# Ver_5.net
KiCad netlist of a schematic drawn in EAGLE
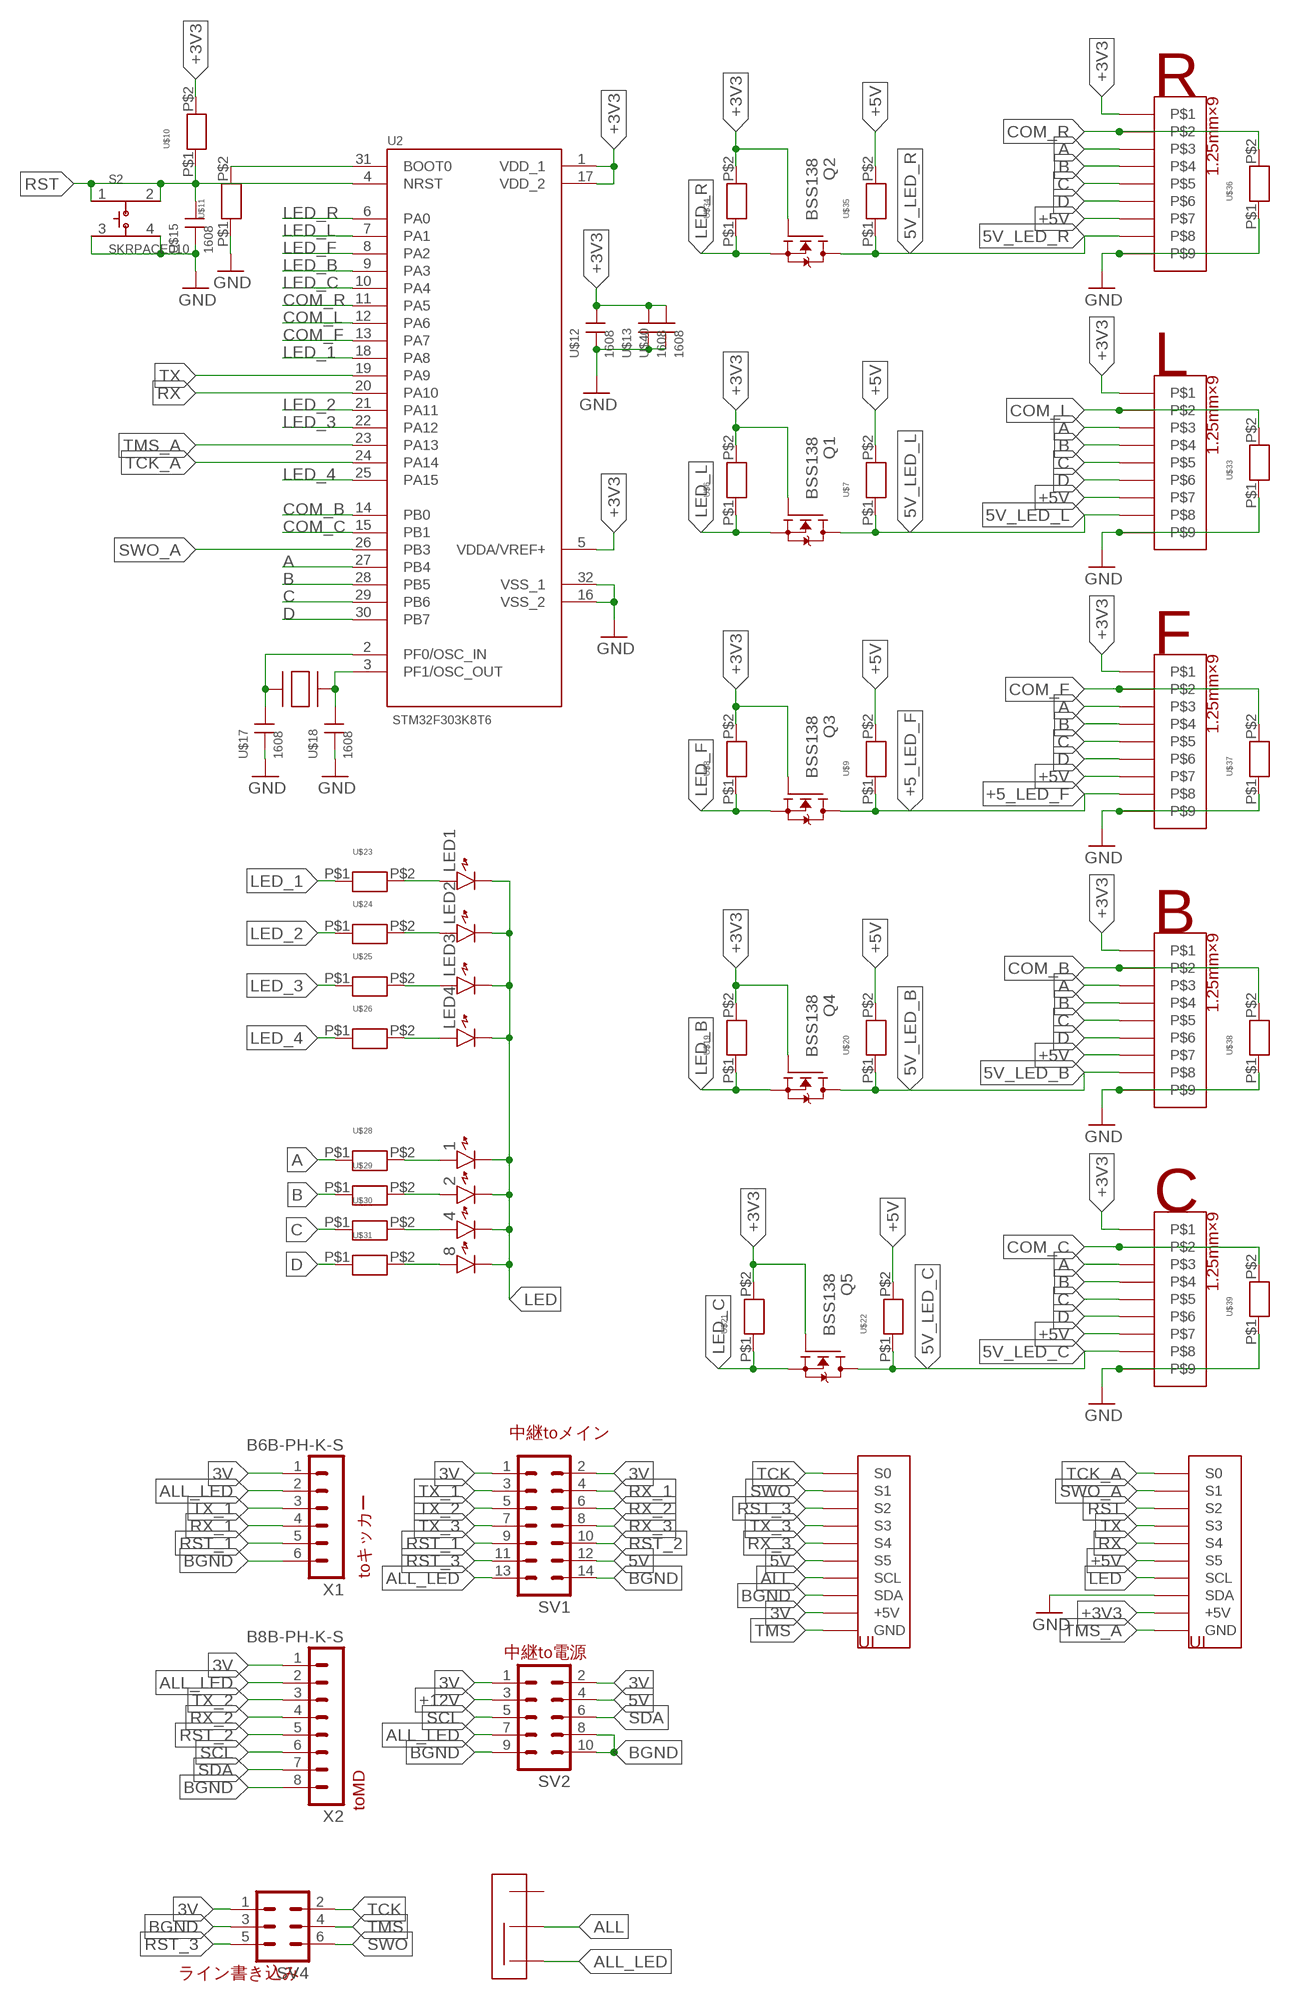
[diagram p0: schematic, sheet 1]

(export (version "E")
  (design (tool "Eeschema 10.0.6"))
  (components
    (comp (ref "1")
      (value "LED1608")
      (footprint "eagle-import:LED1608")
      (libsource (lib "eagle-import") (part "LED1608"))
    )
    (comp (ref "2")
      (value "LED1608")
      (footprint "eagle-import:LED1608")
      (libsource (lib "eagle-import") (part "LED1608"))
    )
    (comp (ref "4")
      (value "LED1608")
      (footprint "eagle-import:LED1608")
      (libsource (lib "eagle-import") (part "LED1608"))
    )
    (comp (ref "8")
      (value "LED1608")
      (footprint "eagle-import:LED1608")
      (libsource (lib "eagle-import") (part "LED1608"))
    )
    (comp (ref "LED1")
      (value "LED1608")
      (footprint "eagle-import:LED1608")
      (libsource (lib "eagle-import") (part "LED1608"))
    )
    (comp (ref "LED2")
      (value "LED1608")
      (footprint "eagle-import:LED1608")
      (libsource (lib "eagle-import") (part "LED1608"))
    )
    (comp (ref "LED3")
      (value "LED1608")
      (footprint "eagle-import:LED1608")
      (libsource (lib "eagle-import") (part "LED1608"))
    )
    (comp (ref "LED4")
      (value "LED1608")
      (footprint "eagle-import:LED1608")
      (libsource (lib "eagle-import") (part "LED1608"))
    )
    (comp (ref "Q1")
      (value "BSS138")
      (footprint "eagle-import:SOT23")
      (fields (field (name "MF") "Fairchild"))
      (libsource (lib "eagle-import") (part "BSS138"))
    )
    (comp (ref "Q2")
      (value "BSS138")
      (footprint "eagle-import:SOT23")
      (fields (field (name "MF") "Fairchild"))
      (libsource (lib "eagle-import") (part "BSS138"))
    )
    (comp (ref "Q3")
      (value "BSS138")
      (footprint "eagle-import:SOT23")
      (fields (field (name "MF") "Fairchild"))
      (libsource (lib "eagle-import") (part "BSS138"))
    )
    (comp (ref "Q4")
      (value "BSS138")
      (footprint "eagle-import:SOT23")
      (fields (field (name "MF") "Fairchild"))
      (libsource (lib "eagle-import") (part "BSS138"))
    )
    (comp (ref "Q5")
      (value "BSS138")
      (footprint "eagle-import:SOT23")
      (fields (field (name "MF") "Fairchild"))
      (libsource (lib "eagle-import") (part "BSS138"))
    )
    (comp (ref "S2")
      (value "SKRPACE010")
      (footprint "eagle-import:SW_SKRPACE010")
      (fields (field (name "MF") "ALPS"))
      (libsource (lib "eagle-import") (part "SKRPACE010"))
    )
    (comp (ref "SV1")
      (value "ML14")
      (footprint "eagle-import:ML14")
      (libsource (lib "eagle-import") (part "ML14"))
    )
    (comp (ref "SV2")
      (value "ML10")
      (footprint "eagle-import:ML10")
      (libsource (lib "eagle-import") (part "ML10"))
    )
    (comp (ref "SV4")
      (value "ML6")
      (footprint "eagle-import:ML6")
      (libsource (lib "eagle-import") (part "ML6"))
    )
    (comp (ref "U$1")
      (value "1MMCON")
      (footprint "eagle-import:1MMCON")
      (libsource (lib "eagle-import") (part "1MMCON"))
    )
    (comp (ref "U$2")
      (value "1MMCON")
      (footprint "eagle-import:1MMCON")
      (libsource (lib "eagle-import") (part "1MMCON"))
    )
    (comp (ref "U$3")
      (value "1MMCON")
      (footprint "eagle-import:1MMCON")
      (libsource (lib "eagle-import") (part "1MMCON"))
    )
    (comp (ref "U$4")
      (value "1MMCON")
      (footprint "eagle-import:1MMCON")
      (libsource (lib "eagle-import") (part "1MMCON"))
    )
    (comp (ref "U$5")
      (value "1MMCON")
      (footprint "eagle-import:1MMCON")
      (libsource (lib "eagle-import") (part "1MMCON"))
    )
    (comp (ref "U$6") (value "R") (footprint "eagle-import:1608") (libsource (lib "eagle-import") (part "R")))
    (comp (ref "U$7") (value "R") (footprint "eagle-import:1608") (libsource (lib "eagle-import") (part "R")))
    (comp (ref "U$8") (value "R") (footprint "eagle-import:1608") (libsource (lib "eagle-import") (part "R")))
    (comp (ref "U$9") (value "R") (footprint "eagle-import:1608") (libsource (lib "eagle-import") (part "R")))
    (comp (ref "U$10")
      (value "R")
      (footprint "eagle-import:1608")
      (libsource (lib "eagle-import") (part "R"))
    )
    (comp (ref "U$11")
      (value "R")
      (footprint "eagle-import:1608")
      (libsource (lib "eagle-import") (part "R"))
    )
    (comp (ref "U$12")
      (value "1608")
      (footprint "eagle-import:CON")
      (libsource (lib "eagle-import") (part "1608"))
    )
    (comp (ref "U$13")
      (value "1608")
      (footprint "eagle-import:CON")
      (libsource (lib "eagle-import") (part "1608"))
    )
    (comp (ref "U$14")
      (value "UI")
      (footprint "eagle-import:UI")
      (libsource (lib "eagle-import") (part "UI"))
    )
    (comp (ref "U$15")
      (value "1608")
      (footprint "eagle-import:CON")
      (libsource (lib "eagle-import") (part "1608"))
    )
    (comp (ref "U$16")
      (value "SUISYOU")
      (footprint "eagle-import:水晶")
      (libsource (lib "eagle-import") (part "SUISYOU"))
    )
    (comp (ref "U$17")
      (value "1608")
      (footprint "eagle-import:CON")
      (libsource (lib "eagle-import") (part "1608"))
    )
    (comp (ref "U$18")
      (value "1608")
      (footprint "eagle-import:CON")
      (libsource (lib "eagle-import") (part "1608"))
    )
    (comp (ref "U$19")
      (value "R")
      (footprint "eagle-import:1608")
      (libsource (lib "eagle-import") (part "R"))
    )
    (comp (ref "U$20")
      (value "R")
      (footprint "eagle-import:1608")
      (libsource (lib "eagle-import") (part "R"))
    )
    (comp (ref "U$21")
      (value "R")
      (footprint "eagle-import:1608")
      (libsource (lib "eagle-import") (part "R"))
    )
    (comp (ref "U$22")
      (value "R")
      (footprint "eagle-import:1608")
      (libsource (lib "eagle-import") (part "R"))
    )
    (comp (ref "U$23")
      (value "R")
      (footprint "eagle-import:1608")
      (libsource (lib "eagle-import") (part "R"))
    )
    (comp (ref "U$24")
      (value "R")
      (footprint "eagle-import:1608")
      (libsource (lib "eagle-import") (part "R"))
    )
    (comp (ref "U$25")
      (value "R")
      (footprint "eagle-import:1608")
      (libsource (lib "eagle-import") (part "R"))
    )
    (comp (ref "U$26")
      (value "R")
      (footprint "eagle-import:1608")
      (libsource (lib "eagle-import") (part "R"))
    )
    (comp (ref "U$27")
      (value "UI")
      (footprint "eagle-import:UI")
      (libsource (lib "eagle-import") (part "UI"))
    )
    (comp (ref "U$28")
      (value "R")
      (footprint "eagle-import:1608")
      (libsource (lib "eagle-import") (part "R"))
    )
    (comp (ref "U$29")
      (value "R")
      (footprint "eagle-import:1608")
      (libsource (lib "eagle-import") (part "R"))
    )
    (comp (ref "U$30")
      (value "R")
      (footprint "eagle-import:1608")
      (libsource (lib "eagle-import") (part "R"))
    )
    (comp (ref "U$31")
      (value "R")
      (footprint "eagle-import:1608")
      (libsource (lib "eagle-import") (part "R"))
    )
    (comp (ref "U$32")
      (value "SSW")
      (footprint "eagle-import:SSW")
      (libsource (lib "eagle-import") (part "SSW"))
    )
    (comp (ref "U$33")
      (value "R")
      (footprint "eagle-import:1608")
      (libsource (lib "eagle-import") (part "R"))
    )
    (comp (ref "U$34")
      (value "R")
      (footprint "eagle-import:1608")
      (libsource (lib "eagle-import") (part "R"))
    )
    (comp (ref "U$35")
      (value "R")
      (footprint "eagle-import:1608")
      (libsource (lib "eagle-import") (part "R"))
    )
    (comp (ref "U$36")
      (value "R")
      (footprint "eagle-import:1608")
      (libsource (lib "eagle-import") (part "R"))
    )
    (comp (ref "U$37")
      (value "R")
      (footprint "eagle-import:1608")
      (libsource (lib "eagle-import") (part "R"))
    )
    (comp (ref "U$38")
      (value "R")
      (footprint "eagle-import:1608")
      (libsource (lib "eagle-import") (part "R"))
    )
    (comp (ref "U$39")
      (value "R")
      (footprint "eagle-import:1608")
      (libsource (lib "eagle-import") (part "R"))
    )
    (comp (ref "U$40")
      (value "1608")
      (footprint "eagle-import:CON")
      (libsource (lib "eagle-import") (part "1608"))
    )
    (comp (ref "U2")
      (value "STM32F303K8T6")
      (footprint "eagle-import:QFP80P900X900X160-32N")
      (fields (field (name "MF") "STMicroelectronics"))
      (libsource (lib "eagle-import") (part "STM32F303K8T6"))
    )
    (comp (ref "X1")
      (value "B6B-PH-K-S")
      (footprint "eagle-import:B6B-PH-K-S")
      (libsource (lib "eagle-import") (part "B6B-PH-K-S"))
    )
    (comp (ref "X2")
      (value "B8B-PH-K-S")
      (footprint "eagle-import:B8B-PH-K-S")
      (libsource (lib "eagle-import") (part "B8B-PH-K-S"))
    )
  )
  (nets
    (net (code "1") (name "+3V3") (class "Default")
      (node (ref "Q1") (pin "1") (pinfunction "G_1") (pintype "passive"))
      (node (ref "Q2") (pin "1") (pinfunction "G_1") (pintype "passive"))
      (node (ref "Q3") (pin "1") (pinfunction "G_1") (pintype "passive"))
      (node (ref "Q4") (pin "1") (pinfunction "G_1") (pintype "passive"))
      (node (ref "Q5") (pin "1") (pinfunction "G_1") (pintype "passive"))
      (node (ref "U$1") (pin "P$1") (pinfunction "P$1_P$1") (pintype "bidirectional"))
      (node (ref "U$10") (pin "P$2") (pinfunction "P$2_P$2") (pintype "bidirectional"))
      (node (ref "U$12") (pin "P$1") (pinfunction "1_P$1") (pintype "bidirectional"))
      (node (ref "U$13") (pin "P$1") (pinfunction "1_P$1") (pintype "bidirectional"))
      (node (ref "U$19") (pin "P$2") (pinfunction "P$2_P$2") (pintype "bidirectional"))
      (node (ref "U$2") (pin "P$1") (pinfunction "P$1_P$1") (pintype "bidirectional"))
      (node (ref "U$21") (pin "P$2") (pinfunction "P$2_P$2") (pintype "bidirectional"))
      (node (ref "U$27") (pin "P$1") (pinfunction "+5V_P$1") (pintype "bidirectional"))
      (node (ref "U$3") (pin "P$1") (pinfunction "P$1_P$1") (pintype "bidirectional"))
      (node (ref "U$34") (pin "P$2") (pinfunction "P$2_P$2") (pintype "bidirectional"))
      (node (ref "U$4") (pin "P$1") (pinfunction "P$1_P$1") (pintype "bidirectional"))
      (node (ref "U$40") (pin "P$1") (pinfunction "1_P$1") (pintype "bidirectional"))
      (node (ref "U$5") (pin "P$1") (pinfunction "P$1_P$1") (pintype "bidirectional"))
      (node (ref "U$6") (pin "P$2") (pinfunction "P$2_P$2") (pintype "bidirectional"))
      (node (ref "U$8") (pin "P$2") (pinfunction "P$2_P$2") (pintype "bidirectional"))
      (node (ref "U2") (pin "1") (pinfunction "VDD_1_1") (pintype "power_in"))
      (node (ref "U2") (pin "17") (pinfunction "VDD_2_17") (pintype "power_in"))
      (node (ref "U2") (pin "5") (pinfunction "VDDA/VREF+_5") (pintype "power_in"))
    )
    (net (code "2") (name "+5V") (class "Default")
      (node (ref "U$1") (pin "P$7") (pinfunction "P$7_P$7") (pintype "bidirectional"))
      (node (ref "U$2") (pin "P$7") (pinfunction "P$7_P$7") (pintype "bidirectional"))
      (node (ref "U$20") (pin "P$2") (pinfunction "P$2_P$2") (pintype "bidirectional"))
      (node (ref "U$22") (pin "P$2") (pinfunction "P$2_P$2") (pintype "bidirectional"))
      (node (ref "U$27") (pin "P$8") (pinfunction "S5_P$8") (pintype "bidirectional"))
      (node (ref "U$3") (pin "P$7") (pinfunction "P$7_P$7") (pintype "bidirectional"))
      (node (ref "U$35") (pin "P$2") (pinfunction "P$2_P$2") (pintype "bidirectional"))
      (node (ref "U$4") (pin "P$7") (pinfunction "P$7_P$7") (pintype "bidirectional"))
      (node (ref "U$5") (pin "P$7") (pinfunction "P$7_P$7") (pintype "bidirectional"))
      (node (ref "U$7") (pin "P$2") (pinfunction "P$2_P$2") (pintype "bidirectional"))
      (node (ref "U$9") (pin "P$2") (pinfunction "P$2_P$2") (pintype "bidirectional"))
    )
    (net (code "3") (name "+5_LED_F") (class "Default")
      (node (ref "Q3") (pin "3") (pinfunction "D_3") (pintype "passive"))
      (node (ref "U$3") (pin "P$8") (pinfunction "P$8_P$8") (pintype "bidirectional"))
      (node (ref "U$9") (pin "P$1") (pinfunction "P$1_P$1") (pintype "bidirectional"))
    )
    (net (code "4") (name "+12V") (class "Default")
      (node (ref "SV2") (pin "3") (pinfunction "3_3") (pintype "passive"))
    )
    (net (code "5") (name "3V") (class "Default")
      (node (ref "SV1") (pin "1") (pinfunction "1_1") (pintype "passive"))
      (node (ref "SV1") (pin "2") (pinfunction "2_2") (pintype "passive"))
      (node (ref "SV2") (pin "1") (pinfunction "1_1") (pintype "passive"))
      (node (ref "SV2") (pin "2") (pinfunction "2_2") (pintype "passive"))
      (node (ref "SV4") (pin "1") (pinfunction "1_1") (pintype "passive"))
      (node (ref "U$14") (pin "P$1") (pinfunction "+5V_P$1") (pintype "bidirectional"))
      (node (ref "X1") (pin "1") (pinfunction "1_1") (pintype "passive"))
      (node (ref "X2") (pin "1") (pinfunction "1_1") (pintype "passive"))
    )
    (net (code "6") (name "5V") (class "Default")
      (node (ref "SV1") (pin "12") (pinfunction "12_12") (pintype "passive"))
      (node (ref "SV2") (pin "4") (pinfunction "4_4") (pintype "passive"))
      (node (ref "U$14") (pin "P$8") (pinfunction "S5_P$8") (pintype "bidirectional"))
    )
    (net (code "7") (name "5V_LED_B") (class "Default")
      (node (ref "Q4") (pin "3") (pinfunction "D_3") (pintype "passive"))
      (node (ref "U$20") (pin "P$1") (pinfunction "P$1_P$1") (pintype "bidirectional"))
      (node (ref "U$4") (pin "P$8") (pinfunction "P$8_P$8") (pintype "bidirectional"))
    )
    (net (code "8") (name "5V_LED_C") (class "Default")
      (node (ref "Q5") (pin "3") (pinfunction "D_3") (pintype "passive"))
      (node (ref "U$22") (pin "P$1") (pinfunction "P$1_P$1") (pintype "bidirectional"))
      (node (ref "U$5") (pin "P$8") (pinfunction "P$8_P$8") (pintype "bidirectional"))
    )
    (net (code "9") (name "5V_LED_L") (class "Default")
      (node (ref "Q1") (pin "3") (pinfunction "D_3") (pintype "passive"))
      (node (ref "U$2") (pin "P$8") (pinfunction "P$8_P$8") (pintype "bidirectional"))
      (node (ref "U$7") (pin "P$1") (pinfunction "P$1_P$1") (pintype "bidirectional"))
    )
    (net (code "10") (name "5V_LED_R") (class "Default")
      (node (ref "Q2") (pin "3") (pinfunction "D_3") (pintype "passive"))
      (node (ref "U$1") (pin "P$8") (pinfunction "P$8_P$8") (pintype "bidirectional"))
      (node (ref "U$35") (pin "P$1") (pinfunction "P$1_P$1") (pintype "bidirectional"))
    )
    (net (code "11") (name "A") (class "Default")
      (node (ref "U$1") (pin "P$3") (pinfunction "P$3_P$3") (pintype "bidirectional"))
      (node (ref "U$2") (pin "P$3") (pinfunction "P$3_P$3") (pintype "bidirectional"))
      (node (ref "U$28") (pin "P$1") (pinfunction "P$1_P$1") (pintype "bidirectional"))
      (node (ref "U$3") (pin "P$3") (pinfunction "P$3_P$3") (pintype "bidirectional"))
      (node (ref "U$4") (pin "P$3") (pinfunction "P$3_P$3") (pintype "bidirectional"))
      (node (ref "U$5") (pin "P$3") (pinfunction "P$3_P$3") (pintype "bidirectional"))
      (node (ref "U2") (pin "27") (pinfunction "PB4_27") (pintype "bidirectional"))
    )
    (net (code "12") (name "ALL") (class "Default")
      (node (ref "U$14") (pin "P$9") (pinfunction "SCL_P$9") (pintype "bidirectional"))
      (node (ref "U$32") (pin "P$3") (pinfunction "P$2_P$3") (pintype "bidirectional"))
    )
    (net (code "13") (name "ALL_LED") (class "Default")
      (node (ref "SV1") (pin "13") (pinfunction "13_13") (pintype "passive"))
      (node (ref "SV2") (pin "7") (pinfunction "7_7") (pintype "passive"))
      (node (ref "U$32") (pin "P$1") (pinfunction "P$1_P$1") (pintype "bidirectional"))
      (node (ref "X1") (pin "2") (pinfunction "2_2") (pintype "passive"))
      (node (ref "X2") (pin "2") (pinfunction "2_2") (pintype "passive"))
    )
    (net (code "14") (name "B") (class "Default")
      (node (ref "U$1") (pin "P$4") (pinfunction "P$4_P$4") (pintype "bidirectional"))
      (node (ref "U$2") (pin "P$4") (pinfunction "P$4_P$4") (pintype "bidirectional"))
      (node (ref "U$29") (pin "P$1") (pinfunction "P$1_P$1") (pintype "bidirectional"))
      (node (ref "U$3") (pin "P$4") (pinfunction "P$4_P$4") (pintype "bidirectional"))
      (node (ref "U$4") (pin "P$4") (pinfunction "P$4_P$4") (pintype "bidirectional"))
      (node (ref "U$5") (pin "P$4") (pinfunction "P$4_P$4") (pintype "bidirectional"))
      (node (ref "U2") (pin "28") (pinfunction "PB5_28") (pintype "bidirectional"))
    )
    (net (code "15") (name "BGND") (class "Default")
      (node (ref "SV1") (pin "14") (pinfunction "14_14") (pintype "passive"))
      (node (ref "SV2") (pin "10") (pinfunction "10_10") (pintype "passive"))
      (node (ref "SV2") (pin "8") (pinfunction "8_8") (pintype "passive"))
      (node (ref "SV2") (pin "9") (pinfunction "9_9") (pintype "passive"))
      (node (ref "SV4") (pin "3") (pinfunction "3_3") (pintype "passive"))
      (node (ref "U$14") (pin "P$10") (pinfunction "SDA_P$10") (pintype "bidirectional"))
      (node (ref "X1") (pin "6") (pinfunction "6_6") (pintype "passive"))
      (node (ref "X2") (pin "8") (pinfunction "8_8") (pintype "passive"))
    )
    (net (code "16") (name "C") (class "Default")
      (node (ref "U$1") (pin "P$5") (pinfunction "P$5_P$5") (pintype "bidirectional"))
      (node (ref "U$2") (pin "P$5") (pinfunction "P$5_P$5") (pintype "bidirectional"))
      (node (ref "U$3") (pin "P$5") (pinfunction "P$5_P$5") (pintype "bidirectional"))
      (node (ref "U$30") (pin "P$1") (pinfunction "P$1_P$1") (pintype "bidirectional"))
      (node (ref "U$4") (pin "P$5") (pinfunction "P$5_P$5") (pintype "bidirectional"))
      (node (ref "U$5") (pin "P$5") (pinfunction "P$5_P$5") (pintype "bidirectional"))
      (node (ref "U2") (pin "29") (pinfunction "PB6_29") (pintype "bidirectional"))
    )
    (net (code "17") (name "COM_B") (class "Default")
      (node (ref "U$38") (pin "P$2") (pinfunction "P$2_P$2") (pintype "bidirectional"))
      (node (ref "U$4") (pin "P$2") (pinfunction "P$2_P$2") (pintype "bidirectional"))
      (node (ref "U2") (pin "14") (pinfunction "PB0_14") (pintype "bidirectional"))
    )
    (net (code "18") (name "COM_C") (class "Default")
      (node (ref "U$39") (pin "P$2") (pinfunction "P$2_P$2") (pintype "bidirectional"))
      (node (ref "U$5") (pin "P$2") (pinfunction "P$2_P$2") (pintype "bidirectional"))
      (node (ref "U2") (pin "15") (pinfunction "PB1_15") (pintype "bidirectional"))
    )
    (net (code "19") (name "COM_F") (class "Default")
      (node (ref "U$3") (pin "P$2") (pinfunction "P$2_P$2") (pintype "bidirectional"))
      (node (ref "U$37") (pin "P$2") (pinfunction "P$2_P$2") (pintype "bidirectional"))
      (node (ref "U2") (pin "13") (pinfunction "PA7_13") (pintype "bidirectional"))
    )
    (net (code "20") (name "COM_L") (class "Default")
      (node (ref "U$2") (pin "P$2") (pinfunction "P$2_P$2") (pintype "bidirectional"))
      (node (ref "U$33") (pin "P$2") (pinfunction "P$2_P$2") (pintype "bidirectional"))
      (node (ref "U2") (pin "12") (pinfunction "PA6_12") (pintype "bidirectional"))
    )
    (net (code "21") (name "COM_R") (class "Default")
      (node (ref "U$1") (pin "P$2") (pinfunction "P$2_P$2") (pintype "bidirectional"))
      (node (ref "U$36") (pin "P$2") (pinfunction "P$2_P$2") (pintype "bidirectional"))
      (node (ref "U2") (pin "11") (pinfunction "PA5_11") (pintype "bidirectional"))
    )
    (net (code "22") (name "D") (class "Default")
      (node (ref "U$1") (pin "P$6") (pinfunction "P$6_P$6") (pintype "bidirectional"))
      (node (ref "U$2") (pin "P$6") (pinfunction "P$6_P$6") (pintype "bidirectional"))
      (node (ref "U$3") (pin "P$6") (pinfunction "P$6_P$6") (pintype "bidirectional"))
      (node (ref "U$31") (pin "P$1") (pinfunction "P$1_P$1") (pintype "bidirectional"))
      (node (ref "U$4") (pin "P$6") (pinfunction "P$6_P$6") (pintype "bidirectional"))
      (node (ref "U$5") (pin "P$6") (pinfunction "P$6_P$6") (pintype "bidirectional"))
      (node (ref "U2") (pin "30") (pinfunction "PB7_30") (pintype "bidirectional"))
    )
    (net (code "23") (name "GND") (class "Default")
      (node (ref "S2") (pin "3") (pinfunction "3_3") (pintype "bidirectional"))
      (node (ref "S2") (pin "4") (pinfunction "4_4") (pintype "bidirectional"))
      (node (ref "U$1") (pin "P$9") (pinfunction "P$9_P$9") (pintype "bidirectional"))
      (node (ref "U$11") (pin "P$1") (pinfunction "P$1_P$1") (pintype "bidirectional"))
      (node (ref "U$12") (pin "P$2") (pinfunction "2_P$2") (pintype "bidirectional"))
      (node (ref "U$13") (pin "P$2") (pinfunction "2_P$2") (pintype "bidirectional"))
      (node (ref "U$15") (pin "P$2") (pinfunction "2_P$2") (pintype "bidirectional"))
      (node (ref "U$17") (pin "P$2") (pinfunction "2_P$2") (pintype "bidirectional"))
      (node (ref "U$18") (pin "P$2") (pinfunction "2_P$2") (pintype "bidirectional"))
      (node (ref "U$2") (pin "P$9") (pinfunction "P$9_P$9") (pintype "bidirectional"))
      (node (ref "U$27") (pin "P$10") (pinfunction "SDA_P$10") (pintype "bidirectional"))
      (node (ref "U$3") (pin "P$9") (pinfunction "P$9_P$9") (pintype "bidirectional"))
      (node (ref "U$33") (pin "P$1") (pinfunction "P$1_P$1") (pintype "bidirectional"))
      (node (ref "U$36") (pin "P$1") (pinfunction "P$1_P$1") (pintype "bidirectional"))
      (node (ref "U$37") (pin "P$1") (pinfunction "P$1_P$1") (pintype "bidirectional"))
      (node (ref "U$38") (pin "P$1") (pinfunction "P$1_P$1") (pintype "bidirectional"))
      (node (ref "U$39") (pin "P$1") (pinfunction "P$1_P$1") (pintype "bidirectional"))
      (node (ref "U$4") (pin "P$9") (pinfunction "P$9_P$9") (pintype "bidirectional"))
      (node (ref "U$40") (pin "P$2") (pinfunction "2_P$2") (pintype "bidirectional"))
      (node (ref "U$5") (pin "P$9") (pinfunction "P$9_P$9") (pintype "bidirectional"))
      (node (ref "U2") (pin "16") (pinfunction "VSS_2_16") (pintype "power_in"))
      (node (ref "U2") (pin "32") (pinfunction "VSS_1_32") (pintype "power_in"))
    )
    (net (code "24") (name "LED") (class "Default")
      (node (ref "1") (pin "K") (pinfunction "K_K") (pintype "passive"))
      (node (ref "2") (pin "K") (pinfunction "K_K") (pintype "passive"))
      (node (ref "4") (pin "K") (pinfunction "K_K") (pintype "passive"))
      (node (ref "8") (pin "K") (pinfunction "K_K") (pintype "passive"))
      (node (ref "LED1") (pin "K") (pinfunction "K_K") (pintype "passive"))
      (node (ref "LED2") (pin "K") (pinfunction "K_K") (pintype "passive"))
      (node (ref "LED3") (pin "K") (pinfunction "K_K") (pintype "passive"))
      (node (ref "LED4") (pin "K") (pinfunction "K_K") (pintype "passive"))
      (node (ref "U$27") (pin "P$9") (pinfunction "SCL_P$9") (pintype "bidirectional"))
    )
    (net (code "25") (name "LED_1") (class "Default")
      (node (ref "U$23") (pin "P$1") (pinfunction "P$1_P$1") (pintype "bidirectional"))
      (node (ref "U2") (pin "18") (pinfunction "PA8_18") (pintype "bidirectional"))
    )
    (net (code "26") (name "LED_2") (class "Default")
      (node (ref "U$24") (pin "P$1") (pinfunction "P$1_P$1") (pintype "bidirectional"))
      (node (ref "U2") (pin "21") (pinfunction "PA11_21") (pintype "bidirectional"))
    )
    (net (code "27") (name "LED_3") (class "Default")
      (node (ref "U$25") (pin "P$1") (pinfunction "P$1_P$1") (pintype "bidirectional"))
      (node (ref "U2") (pin "22") (pinfunction "PA12_22") (pintype "bidirectional"))
    )
    (net (code "28") (name "LED_4") (class "Default")
      (node (ref "U$26") (pin "P$1") (pinfunction "P$1_P$1") (pintype "bidirectional"))
      (node (ref "U2") (pin "25") (pinfunction "PA15_25") (pintype "bidirectional"))
    )
    (net (code "29") (name "LED_B") (class "Default")
      (node (ref "Q4") (pin "2") (pinfunction "S_2") (pintype "passive"))
      (node (ref "U$19") (pin "P$1") (pinfunction "P$1_P$1") (pintype "bidirectional"))
      (node (ref "U2") (pin "9") (pinfunction "PA3_9") (pintype "bidirectional"))
    )
    (net (code "30") (name "LED_C") (class "Default")
      (node (ref "Q5") (pin "2") (pinfunction "S_2") (pintype "passive"))
      (node (ref "U$21") (pin "P$1") (pinfunction "P$1_P$1") (pintype "bidirectional"))
      (node (ref "U2") (pin "10") (pinfunction "PA4_10") (pintype "bidirectional"))
    )
    (net (code "31") (name "LED_F") (class "Default")
      (node (ref "Q3") (pin "2") (pinfunction "S_2") (pintype "passive"))
      (node (ref "U$8") (pin "P$1") (pinfunction "P$1_P$1") (pintype "bidirectional"))
      (node (ref "U2") (pin "8") (pinfunction "PA2_8") (pintype "bidirectional"))
    )
    (net (code "32") (name "LED_L") (class "Default")
      (node (ref "Q1") (pin "2") (pinfunction "S_2") (pintype "passive"))
      (node (ref "U$6") (pin "P$1") (pinfunction "P$1_P$1") (pintype "bidirectional"))
      (node (ref "U2") (pin "7") (pinfunction "PA1_7") (pintype "bidirectional"))
    )
    (net (code "33") (name "LED_R") (class "Default")
      (node (ref "Q2") (pin "2") (pinfunction "S_2") (pintype "passive"))
      (node (ref "U$34") (pin "P$1") (pinfunction "P$1_P$1") (pintype "bidirectional"))
      (node (ref "U2") (pin "6") (pinfunction "PA0_6") (pintype "bidirectional"))
    )
    (net (code "34") (name "Net-(1-PadA)") (class "Default")
      (node (ref "1") (pin "A") (pinfunction "A_A") (pintype "passive"))
      (node (ref "U$28") (pin "P$2") (pinfunction "P$2_P$2") (pintype "bidirectional"))
    )
    (net (code "35") (name "Net-(2-PadA)") (class "Default")
      (node (ref "2") (pin "A") (pinfunction "A_A") (pintype "passive"))
      (node (ref "U$29") (pin "P$2") (pinfunction "P$2_P$2") (pintype "bidirectional"))
    )
    (net (code "36") (name "Net-(4-PadA)") (class "Default")
      (node (ref "4") (pin "A") (pinfunction "A_A") (pintype "passive"))
      (node (ref "U$30") (pin "P$2") (pinfunction "P$2_P$2") (pintype "bidirectional"))
    )
    (net (code "37") (name "Net-(8-PadA)") (class "Default")
      (node (ref "8") (pin "A") (pinfunction "A_A") (pintype "passive"))
      (node (ref "U$31") (pin "P$2") (pinfunction "P$2_P$2") (pintype "bidirectional"))
    )
    (net (code "38") (name "Net-(LED1-PadA)") (class "Default")
      (node (ref "LED1") (pin "A") (pinfunction "A_A") (pintype "passive"))
      (node (ref "U$23") (pin "P$2") (pinfunction "P$2_P$2") (pintype "bidirectional"))
    )
    (net (code "39") (name "Net-(LED2-PadA)") (class "Default")
      (node (ref "LED2") (pin "A") (pinfunction "A_A") (pintype "passive"))
      (node (ref "U$24") (pin "P$2") (pinfunction "P$2_P$2") (pintype "bidirectional"))
    )
    (net (code "40") (name "Net-(LED3-PadA)") (class "Default")
      (node (ref "LED3") (pin "A") (pinfunction "A_A") (pintype "passive"))
      (node (ref "U$25") (pin "P$2") (pinfunction "P$2_P$2") (pintype "bidirectional"))
    )
    (net (code "41") (name "Net-(LED4-PadA)") (class "Default")
      (node (ref "LED4") (pin "A") (pinfunction "A_A") (pintype "passive"))
      (node (ref "U$26") (pin "P$2") (pinfunction "P$2_P$2") (pintype "bidirectional"))
    )
    (net (code "42") (name "Net-(U$17-1)") (class "Default")
      (node (ref "U$16") (pin "P$1") (pinfunction "P$1_P$1") (pintype "bidirectional"))
      (node (ref "U$17") (pin "P$1") (pinfunction "1_P$1") (pintype "bidirectional"))
      (node (ref "U2") (pin "2") (pinfunction "PF0/OSC_IN_2") (pintype "bidirectional"))
    )
    (net (code "43") (name "Net-(U$18-1)") (class "Default")
      (node (ref "U$16") (pin "P$2") (pinfunction "P$2_P$2") (pintype "bidirectional"))
      (node (ref "U$18") (pin "P$1") (pinfunction "1_P$1") (pintype "bidirectional"))
      (node (ref "U2") (pin "3") (pinfunction "PF1/OSC_OUT_3") (pintype "bidirectional"))
    )
    (net (code "44") (name "Net-(U2-BOOT0)") (class "Default")
      (node (ref "U$11") (pin "P$2") (pinfunction "P$2_P$2") (pintype "bidirectional"))
      (node (ref "U2") (pin "31") (pinfunction "BOOT0_31") (pintype "input"))
    )
    (net (code "45") (name "RST") (class "Default")
      (node (ref "S2") (pin "1") (pinfunction "1_1") (pintype "bidirectional"))
      (node (ref "S2") (pin "2") (pinfunction "2_2") (pintype "bidirectional"))
      (node (ref "U$10") (pin "P$1") (pinfunction "P$1_P$1") (pintype "bidirectional"))
      (node (ref "U$15") (pin "P$1") (pinfunction "1_P$1") (pintype "bidirectional"))
      (node (ref "U$27") (pin "P$5") (pinfunction "S2_P$5") (pintype "bidirectional"))
      (node (ref "U2") (pin "4") (pinfunction "NRST_4") (pintype "bidirectional"))
    )
    (net (code "46") (name "RST_1") (class "Default")
      (node (ref "SV1") (pin "9") (pinfunction "9_9") (pintype "passive"))
      (node (ref "X1") (pin "5") (pinfunction "5_5") (pintype "passive"))
    )
    (net (code "47") (name "RST_2") (class "Default")
      (node (ref "SV1") (pin "10") (pinfunction "10_10") (pintype "passive"))
      (node (ref "X2") (pin "5") (pinfunction "5_5") (pintype "passive"))
    )
    (net (code "48") (name "RST_3") (class "Default")
      (node (ref "SV1") (pin "11") (pinfunction "11_11") (pintype "passive"))
      (node (ref "SV4") (pin "5") (pinfunction "5_5") (pintype "passive"))
      (node (ref "U$14") (pin "P$5") (pinfunction "S2_P$5") (pintype "bidirectional"))
    )
    (net (code "49") (name "RX") (class "Default")
      (node (ref "U$27") (pin "P$7") (pinfunction "S4_P$7") (pintype "bidirectional"))
      (node (ref "U2") (pin "20") (pinfunction "PA10_20") (pintype "bidirectional"))
    )
    (net (code "50") (name "RX_1") (class "Default")
      (node (ref "SV1") (pin "4") (pinfunction "4_4") (pintype "passive"))
      (node (ref "X1") (pin "4") (pinfunction "4_4") (pintype "passive"))
    )
    (net (code "51") (name "RX_2") (class "Default")
      (node (ref "SV1") (pin "6") (pinfunction "6_6") (pintype "passive"))
      (node (ref "X2") (pin "4") (pinfunction "4_4") (pintype "passive"))
    )
    (net (code "52") (name "RX_3") (class "Default")
      (node (ref "SV1") (pin "8") (pinfunction "8_8") (pintype "passive"))
      (node (ref "U$14") (pin "P$7") (pinfunction "S4_P$7") (pintype "bidirectional"))
    )
    (net (code "53") (name "SCL") (class "Default")
      (node (ref "SV2") (pin "5") (pinfunction "5_5") (pintype "passive"))
      (node (ref "X2") (pin "6") (pinfunction "6_6") (pintype "passive"))
    )
    (net (code "54") (name "SDA") (class "Default")
      (node (ref "SV2") (pin "6") (pinfunction "6_6") (pintype "passive"))
      (node (ref "X2") (pin "7") (pinfunction "7_7") (pintype "passive"))
    )
    (net (code "55") (name "SWO") (class "Default")
      (node (ref "SV4") (pin "6") (pinfunction "6_6") (pintype "passive"))
      (node (ref "U$14") (pin "P$4") (pinfunction "S1_P$4") (pintype "bidirectional"))
    )
    (net (code "56") (name "SWO_A") (class "Default")
      (node (ref "U$27") (pin "P$4") (pinfunction "S1_P$4") (pintype "bidirectional"))
      (node (ref "U2") (pin "26") (pinfunction "PB3_26") (pintype "bidirectional"))
    )
    (net (code "57") (name "TCK") (class "Default")
      (node (ref "SV4") (pin "2") (pinfunction "2_2") (pintype "passive"))
      (node (ref "U$14") (pin "P$3") (pinfunction "S0_P$3") (pintype "bidirectional"))
    )
    (net (code "58") (name "TCK_A") (class "Default")
      (node (ref "U$27") (pin "P$3") (pinfunction "S0_P$3") (pintype "bidirectional"))
      (node (ref "U2") (pin "24") (pinfunction "PA14_24") (pintype "bidirectional"))
    )
    (net (code "59") (name "TMS") (class "Default")
      (node (ref "SV4") (pin "4") (pinfunction "4_4") (pintype "passive"))
      (node (ref "U$14") (pin "P$2") (pinfunction "GND_P$2") (pintype "bidirectional"))
    )
    (net (code "60") (name "TMS_A") (class "Default")
      (node (ref "U$27") (pin "P$2") (pinfunction "GND_P$2") (pintype "bidirectional"))
      (node (ref "U2") (pin "23") (pinfunction "PA13_23") (pintype "bidirectional"))
    )
    (net (code "61") (name "TX") (class "Default")
      (node (ref "U$27") (pin "P$6") (pinfunction "S3_P$6") (pintype "bidirectional"))
      (node (ref "U2") (pin "19") (pinfunction "PA9_19") (pintype "bidirectional"))
    )
    (net (code "62") (name "TX_1") (class "Default")
      (node (ref "SV1") (pin "3") (pinfunction "3_3") (pintype "passive"))
      (node (ref "X1") (pin "3") (pinfunction "3_3") (pintype "passive"))
    )
    (net (code "63") (name "TX_2") (class "Default")
      (node (ref "SV1") (pin "5") (pinfunction "5_5") (pintype "passive"))
      (node (ref "X2") (pin "3") (pinfunction "3_3") (pintype "passive"))
    )
    (net (code "64") (name "TX_3") (class "Default")
      (node (ref "SV1") (pin "7") (pinfunction "7_7") (pintype "passive"))
      (node (ref "U$14") (pin "P$6") (pinfunction "S3_P$6") (pintype "bidirectional"))
    )
    (net (code "65") (name "unconnected-(U$32-P$3-PadP$2)") (class "Default")
      (node (ref "U$32") (pin "P$2") (pinfunction "P$3_P$2") (pintype "bidirectional"))
    )
  )
)
